# QuantumDice.net
KiCad netlist of a schematic drawn in EAGLE
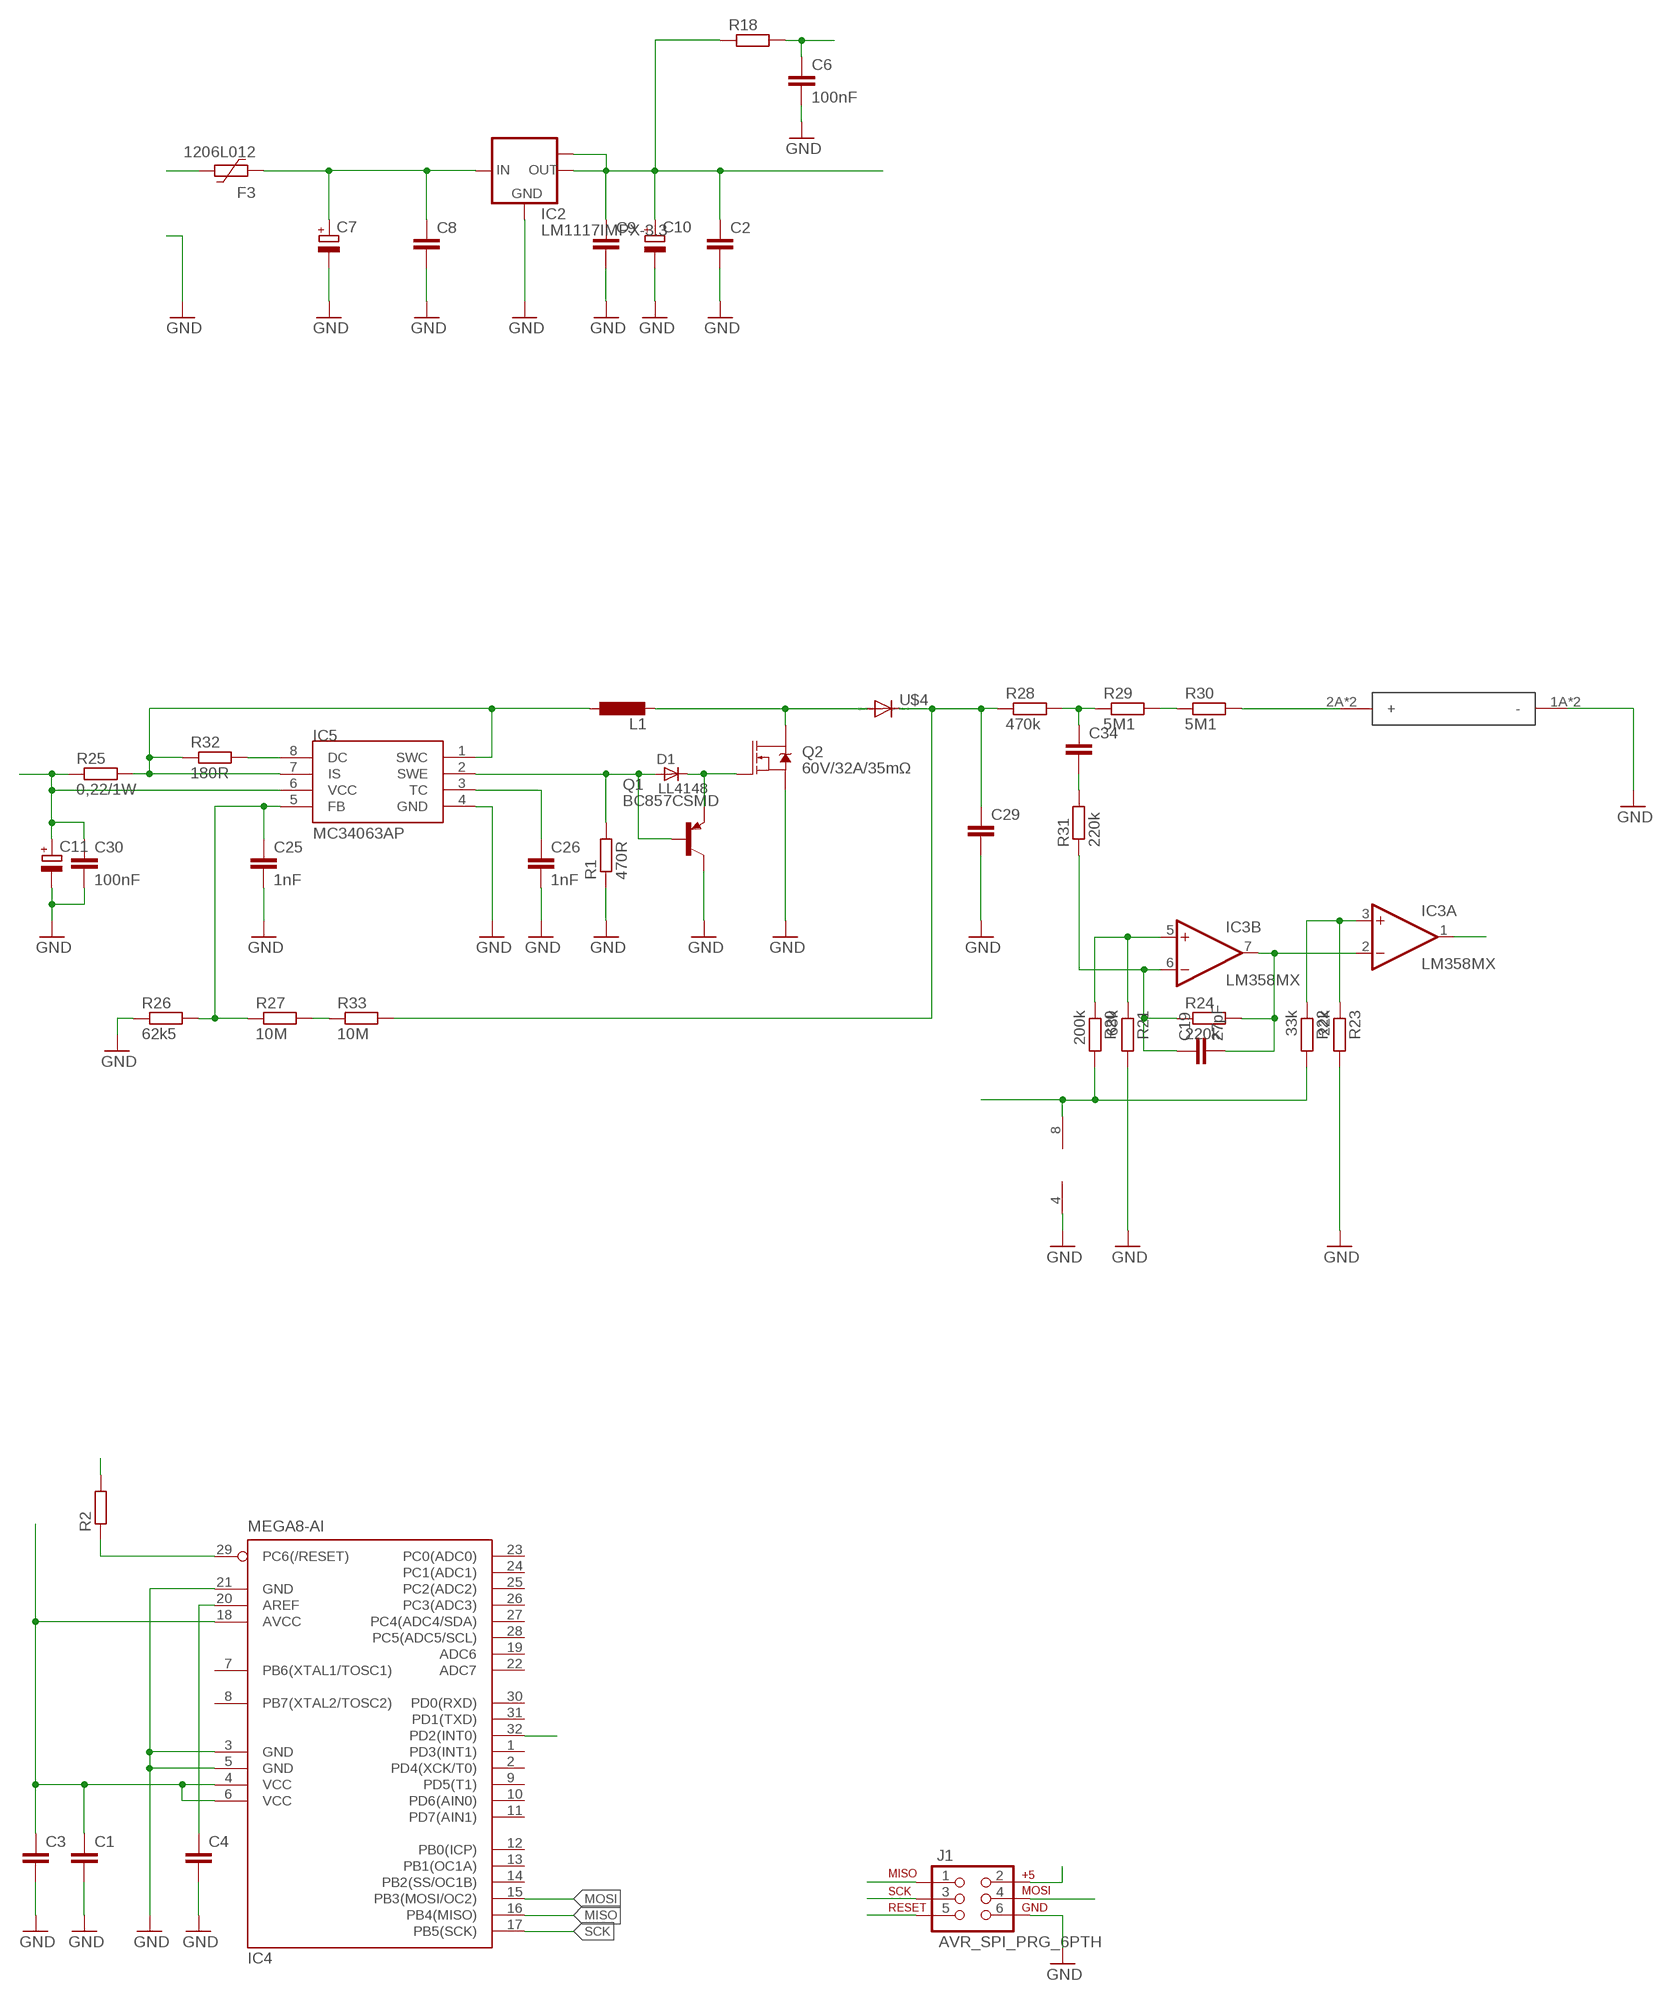
[diagram p0: schematic, sheet 1]

(export (version "E")
  (design (tool "Eeschema 10.0.6"))
  (components
    (comp (ref "C1")
      (value "C-EUC0603")
      (footprint "eagle-import:C0603")
      (libsource (lib "eagle-import") (part "C-EUC0603"))
    )
    (comp (ref "C2")
      (value "C-EUC0603")
      (footprint "eagle-import:C0603")
      (libsource (lib "eagle-import") (part "C-EUC0603"))
    )
    (comp (ref "C3")
      (value "C-EUC0603")
      (footprint "eagle-import:C0603")
      (libsource (lib "eagle-import") (part "C-EUC0603"))
    )
    (comp (ref "C4")
      (value "C-EUC0603")
      (footprint "eagle-import:C0603")
      (libsource (lib "eagle-import") (part "C-EUC0603"))
    )
    (comp (ref "C6")
      (value "100nF")
      (footprint "eagle-import:C0603")
      (libsource (lib "eagle-import") (part "C-EUC0603"))
    )
    (comp (ref "C7")
      (value "CPOL-EUSMCC")
      (footprint "eagle-import:SMC_C")
      (libsource (lib "eagle-import") (part "CPOL-EUSMCC"))
    )
    (comp (ref "C8")
      (value "C-EUC1206")
      (footprint "eagle-import:C1206")
      (libsource (lib "eagle-import") (part "C-EUC1206"))
    )
    (comp (ref "C9")
      (value "C-EUC1206")
      (footprint "eagle-import:C1206")
      (libsource (lib "eagle-import") (part "C-EUC1206"))
    )
    (comp (ref "C10")
      (value "CPOL-EUSMCC")
      (footprint "eagle-import:SMC_C")
      (libsource (lib "eagle-import") (part "CPOL-EUSMCC"))
    )
    (comp (ref "C11")
      (value "CPOL-EUSMCE")
      (footprint "eagle-import:SMC_E")
      (libsource (lib "eagle-import") (part "CPOL-EUSMCE"))
    )
    (comp (ref "C19")
      (value "27pF")
      (footprint "eagle-import:C0603")
      (libsource (lib "eagle-import") (part "C-EUC0603"))
    )
    (comp (ref "C25")
      (value "1nF")
      (footprint "eagle-import:C0603")
      (libsource (lib "eagle-import") (part "C-EUC0603"))
    )
    (comp (ref "C26")
      (value "1nF")
      (footprint "eagle-import:C0603")
      (libsource (lib "eagle-import") (part "C-EUC0603"))
    )
    (comp (ref "C29")
      (value "C-EU225-113X268")
      (footprint "eagle-import:C225-113X268")
      (libsource (lib "eagle-import") (part "C-EU225-113X268"))
    )
    (comp (ref "C30")
      (value "100nF")
      (footprint "eagle-import:C0603")
      (libsource (lib "eagle-import") (part "C-EUC0603"))
    )
    (comp (ref "C34")
      (value "C-EU050-024X044")
      (footprint "eagle-import:C050-024X044")
      (libsource (lib "eagle-import") (part "C-EU050-024X044"))
    )
    (comp (ref "D1")
      (value "LL4148")
      (footprint "eagle-import:SOD80_DO213AA_MINIMELF")
      (libsource (lib "eagle-import") (part "LL4148"))
    )
    (comp (ref "F3")
      (value "1206L012")
      (footprint "eagle-import:1206L")
      (fields (field (name "MF") "Littelfuse"))
      (libsource (lib "eagle-import") (part "?1206L012"))
    )
    (comp (ref "IC2")
      (value "LM1117IMPX-3.3")
      (footprint "eagle-import:SOT223")
      (libsource (lib "eagle-import") (part "LM1117IMPX-3.3"))
    )
    (comp (ref "IC3")
      (value "LM358MX")
      (footprint "eagle-import:SO08")
      (libsource (lib "eagle-import") (part "LM358MX"))
    )
    (comp (ref "IC4")
      (value "MEGA8-AI")
      (footprint "eagle-import:TQFP32-08")
      (fields (field (name "MPN") "ATMEGA8-16AU"))
      (libsource (lib "eagle-import") (part "MEGA8-AI"))
    )
    (comp (ref "IC5")
      (value "MC34063AP")
      (footprint "eagle-import:DIL08")
      (libsource (lib "eagle-import") (part "MC34063AP"))
    )
    (comp (ref "J1")
      (value "AVR_SPI_PRG_6PTH")
      (footprint "eagle-import:2X3")
      (libsource (lib "eagle-import") (part "AVR_SPI_PRG_6PTH"))
    )
    (comp (ref "L1")
      (value "L-EU6000-XXX-RC")
      (footprint "eagle-import:6000-XXXX-RC")
      (libsource (lib "eagle-import") (part "L-EU6000-XXX-RC"))
    )
    (comp (ref "Q1")
      (value "BC857CSMD")
      (footprint "eagle-import:SOT23-BEC")
      (libsource (lib "eagle-import") (part "BC857SMDC"))
    )
    (comp (ref "Q2")
      (value "60V/32A/35mΩ")
      (footprint "eagle-import:TO220V")
      (libsource (lib "eagle-import") (part "MOSFET-NCH-FQP30N06L"))
    )
    (comp (ref "R1")
      (value "470R")
      (footprint "eagle-import:R1206")
      (libsource (lib "eagle-import") (part "R-EU_R1206"))
    )
    (comp (ref "R2")
      (value "R-EU_R0603")
      (footprint "eagle-import:R0603")
      (libsource (lib "eagle-import") (part "R-EU_R0603"))
    )
    (comp (ref "R18")
      (value "R-EU_R1206")
      (footprint "eagle-import:R1206")
      (libsource (lib "eagle-import") (part "R-EU_R1206"))
    )
    (comp (ref "R20")
      (value "200k")
      (footprint "eagle-import:R0603")
      (libsource (lib "eagle-import") (part "R-EU_R0603"))
    )
    (comp (ref "R21")
      (value "68k")
      (footprint "eagle-import:R0603")
      (libsource (lib "eagle-import") (part "R-EU_R0603"))
    )
    (comp (ref "R22")
      (value "33k")
      (footprint "eagle-import:R1206")
      (libsource (lib "eagle-import") (part "R-EU_R1206"))
    )
    (comp (ref "R23")
      (value "22k")
      (footprint "eagle-import:R0603")
      (libsource (lib "eagle-import") (part "R-EU_R0603"))
    )
    (comp (ref "R24")
      (value "220k")
      (footprint "eagle-import:R0603")
      (libsource (lib "eagle-import") (part "R-EU_R0603"))
    )
    (comp (ref "R25")
      (value "0,22/1W")
      (footprint "eagle-import:R2010")
      (libsource (lib "eagle-import") (part "R-EU_R2010"))
    )
    (comp (ref "R26")
      (value "62k5")
      (footprint "eagle-import:R1206")
      (libsource (lib "eagle-import") (part "R-EU_R1206"))
    )
    (comp (ref "R27")
      (value "10M")
      (footprint "eagle-import:R2512")
      (libsource (lib "eagle-import") (part "R-EU_R2512"))
    )
    (comp (ref "R28")
      (value "470k")
      (footprint "eagle-import:R2512")
      (libsource (lib "eagle-import") (part "R-EU_R2512"))
    )
    (comp (ref "R29")
      (value "5M1")
      (footprint "eagle-import:R2512")
      (libsource (lib "eagle-import") (part "R-EU_R2512"))
    )
    (comp (ref "R30")
      (value "5M1")
      (footprint "eagle-import:R2512")
      (libsource (lib "eagle-import") (part "R-EU_R2512"))
    )
    (comp (ref "R31")
      (value "220k")
      (footprint "eagle-import:R0805")
      (libsource (lib "eagle-import") (part "R-EU_R0805"))
    )
    (comp (ref "R32")
      (value "180R")
      (footprint "eagle-import:R0805")
      (libsource (lib "eagle-import") (part "R-EU_R0805"))
    )
    (comp (ref "R33")
      (value "10M")
      (footprint "eagle-import:R2512")
      (libsource (lib "eagle-import") (part "R-EU_R2512"))
    )
    (comp (ref "U$4")
      (value "DIODE-MELF-MLL41")
      (footprint "eagle-import:MELF-MLL41")
      (libsource (lib "eagle-import") (part "DIODE-MELF-MLL41"))
    )
    (comp (ref "U$5")
      (value "STS5")
      (footprint "eagle-import:GEIGERTUBE")
      (libsource (lib "eagle-import") (part "STS5"))
    )
  )
  (nets
    (net (code "1") (name "/9V") (class "Default")
      (node (ref "C11") (pin "+") (pinfunction "+_+") (pintype "passive"))
      (node (ref "C30") (pin "1") (pinfunction "1_1") (pintype "passive"))
      (node (ref "C7") (pin "+") (pinfunction "+_+") (pintype "passive"))
      (node (ref "C8") (pin "1") (pinfunction "1_1") (pintype "passive"))
      (node (ref "F3") (pin "2") (pinfunction "2_2") (pintype "passive"))
      (node (ref "IC2") (pin "3") (pinfunction "IN_3") (pintype "input"))
      (node (ref "IC5") (pin "6") (pinfunction "VCC_6") (pintype "passive"))
      (node (ref "R25") (pin "1") (pinfunction "1_1") (pintype "passive"))
    )
    (net (code "2") (name "/A_5V") (class "Default")
      (node (ref "C6") (pin "1") (pinfunction "1_1") (pintype "passive"))
      (node (ref "IC3") (pin "8") (pinfunction "V+_8") (pintype "power_in"))
      (node (ref "R18") (pin "2") (pinfunction "2_2") (pintype "passive"))
      (node (ref "R20") (pin "2") (pinfunction "2_2") (pintype "passive"))
      (node (ref "R22") (pin "2") (pinfunction "2_2") (pintype "passive"))
    )
    (net (code "3") (name "/CPM") (class "Default")
      (node (ref "IC3") (pin "1") (pinfunction "OUT_1") (pintype "output"))
      (node (ref "IC4") (pin "32") (pinfunction "PD2(INT0)_32") (pintype "bidirectional"))
    )
    (net (code "4") (name "/RESET") (class "Default")
      (node (ref "IC4") (pin "29") (pinfunction "PC6(/RESET)_29") (pintype "bidirectional"))
      (node (ref "J1") (pin "5") (pinfunction "5_5") (pintype "passive"))
      (node (ref "R2") (pin "1") (pinfunction "1_1") (pintype "passive"))
    )
    (net (code "5") (name "/_5V") (class "Default")
      (node (ref "C1") (pin "1") (pinfunction "1_1") (pintype "passive"))
      (node (ref "C10") (pin "+") (pinfunction "+_+") (pintype "passive"))
      (node (ref "C2") (pin "1") (pinfunction "1_1") (pintype "passive"))
      (node (ref "C3") (pin "1") (pinfunction "1_1") (pintype "passive"))
      (node (ref "C9") (pin "1") (pinfunction "1_1") (pintype "passive"))
      (node (ref "IC2") (pin "2") (pinfunction "OUT_2") (pintype "passive"))
      (node (ref "IC2") (pin "TAB") (pinfunction "OUT1_TAB") (pintype "passive"))
      (node (ref "IC4") (pin "18") (pinfunction "AVCC_18") (pintype "power_in"))
      (node (ref "IC4") (pin "4") (pinfunction "VCC_4") (pintype "power_in"))
      (node (ref "IC4") (pin "6") (pinfunction "VCC_6") (pintype "power_in"))
      (node (ref "J1") (pin "2") (pinfunction "2_2") (pintype "passive"))
      (node (ref "R18") (pin "1") (pinfunction "1_1") (pintype "passive"))
      (node (ref "R2") (pin "2") (pinfunction "2_2") (pintype "passive"))
    )
    (net (code "6") (name "GND") (class "Default")
      (node (ref "C1") (pin "2") (pinfunction "2_2") (pintype "passive"))
      (node (ref "C10") (pin "-") (pinfunction "-_-") (pintype "passive"))
      (node (ref "C11") (pin "-") (pinfunction "-_-") (pintype "passive"))
      (node (ref "C2") (pin "2") (pinfunction "2_2") (pintype "passive"))
      (node (ref "C25") (pin "2") (pinfunction "2_2") (pintype "passive"))
      (node (ref "C26") (pin "2") (pinfunction "2_2") (pintype "passive"))
      (node (ref "C29") (pin "2") (pinfunction "2_2") (pintype "passive"))
      (node (ref "C3") (pin "2") (pinfunction "2_2") (pintype "passive"))
      (node (ref "C30") (pin "2") (pinfunction "2_2") (pintype "passive"))
      (node (ref "C4") (pin "2") (pinfunction "2_2") (pintype "passive"))
      (node (ref "C6") (pin "2") (pinfunction "2_2") (pintype "passive"))
      (node (ref "C7") (pin "-") (pinfunction "-_-") (pintype "passive"))
      (node (ref "C8") (pin "2") (pinfunction "2_2") (pintype "passive"))
      (node (ref "C9") (pin "2") (pinfunction "2_2") (pintype "passive"))
      (node (ref "IC2") (pin "1") (pinfunction "GND_1") (pintype "input"))
      (node (ref "IC3") (pin "4") (pinfunction "V-_4") (pintype "power_in"))
      (node (ref "IC4") (pin "21") (pinfunction "GND_21") (pintype "power_in"))
      (node (ref "IC4") (pin "3") (pinfunction "GND_3") (pintype "power_in"))
      (node (ref "IC4") (pin "5") (pinfunction "GND_5") (pintype "power_in"))
      (node (ref "IC5") (pin "4") (pinfunction "GND_4") (pintype "passive"))
      (node (ref "J1") (pin "6") (pinfunction "6_6") (pintype "passive"))
      (node (ref "Q1") (pin "C") (pinfunction "C_C") (pintype "passive"))
      (node (ref "Q2") (pin "3") (pinfunction "S_3") (pintype "bidirectional"))
      (node (ref "R1") (pin "1") (pinfunction "1_1") (pintype "passive"))
      (node (ref "R21") (pin "2") (pinfunction "2_2") (pintype "passive"))
      (node (ref "R23") (pin "2") (pinfunction "2_2") (pintype "passive"))
      (node (ref "R26") (pin "1") (pinfunction "1_1") (pintype "passive"))
      (node (ref "U$5") (pin "1A") (pinfunction "-_1A") (pintype "bidirectional"))
      (node (ref "U$5") (pin "1B") (pinfunction "-_1B") (pintype "bidirectional"))
    )
    (net (code "7") (name "MISO") (class "Default")
      (node (ref "IC4") (pin "16") (pinfunction "PB4(MISO)_16") (pintype "bidirectional"))
      (node (ref "J1") (pin "1") (pinfunction "1_1") (pintype "passive"))
    )
    (net (code "8") (name "MOSI") (class "Default")
      (node (ref "IC4") (pin "15") (pinfunction "PB3(MOSI/OC2)_15") (pintype "bidirectional"))
      (node (ref "J1") (pin "4") (pinfunction "4_4") (pintype "passive"))
    )
    (net (code "9") (name "Net-(C29-Pad1)") (class "Default")
      (node (ref "C29") (pin "1") (pinfunction "1_1") (pintype "passive"))
      (node (ref "R28") (pin "1") (pinfunction "1_1") (pintype "passive"))
      (node (ref "R33") (pin "2") (pinfunction "2_2") (pintype "passive"))
      (node (ref "U$4") (pin "C") (pinfunction "C_C") (pintype "passive"))
    )
    (net (code "10") (name "Net-(C34-Pad1)") (class "Default")
      (node (ref "C34") (pin "1") (pinfunction "1_1") (pintype "passive"))
      (node (ref "R28") (pin "2") (pinfunction "2_2") (pintype "passive"))
      (node (ref "R29") (pin "1") (pinfunction "1_1") (pintype "passive"))
    )
    (net (code "11") (name "Net-(C34-Pad2)") (class "Default")
      (node (ref "C34") (pin "2") (pinfunction "2_2") (pintype "passive"))
      (node (ref "R31") (pin "2") (pinfunction "2_2") (pintype "passive"))
    )
    (net (code "12") (name "Net-(IC3A-+IN)") (class "Default")
      (node (ref "IC3") (pin "3") (pinfunction "+IN_3") (pintype "input"))
      (node (ref "R22") (pin "1") (pinfunction "1_1") (pintype "passive"))
      (node (ref "R23") (pin "1") (pinfunction "1_1") (pintype "passive"))
    )
    (net (code "13") (name "Net-(IC3A--IN)") (class "Default")
      (node (ref "C19") (pin "2") (pinfunction "2_2") (pintype "passive"))
      (node (ref "IC3") (pin "2") (pinfunction "-IN_2") (pintype "input"))
      (node (ref "IC3") (pin "7") (pinfunction "OUT_7") (pintype "output"))
      (node (ref "R24") (pin "2") (pinfunction "2_2") (pintype "passive"))
    )
    (net (code "14") (name "Net-(IC3B-+IN)") (class "Default")
      (node (ref "IC3") (pin "5") (pinfunction "+IN_5") (pintype "input"))
      (node (ref "R20") (pin "1") (pinfunction "1_1") (pintype "passive"))
      (node (ref "R21") (pin "1") (pinfunction "1_1") (pintype "passive"))
    )
    (net (code "15") (name "Net-(IC3B--IN)") (class "Default")
      (node (ref "C19") (pin "1") (pinfunction "1_1") (pintype "passive"))
      (node (ref "IC3") (pin "6") (pinfunction "-IN_6") (pintype "input"))
      (node (ref "R24") (pin "1") (pinfunction "1_1") (pintype "passive"))
      (node (ref "R31") (pin "1") (pinfunction "1_1") (pintype "passive"))
    )
    (net (code "16") (name "Net-(IC4-AREF)") (class "Default")
      (node (ref "C4") (pin "1") (pinfunction "1_1") (pintype "passive"))
      (node (ref "IC4") (pin "20") (pinfunction "AREF_20") (pintype "passive"))
    )
    (net (code "17") (name "Net-(IC5-DC)") (class "Default")
      (node (ref "IC5") (pin "8") (pinfunction "DC_8") (pintype "passive"))
      (node (ref "R32") (pin "2") (pinfunction "2_2") (pintype "passive"))
    )
    (net (code "18") (name "Net-(IC5-FB)") (class "Default")
      (node (ref "C25") (pin "1") (pinfunction "1_1") (pintype "passive"))
      (node (ref "IC5") (pin "5") (pinfunction "FB_5") (pintype "passive"))
      (node (ref "R26") (pin "2") (pinfunction "2_2") (pintype "passive"))
      (node (ref "R27") (pin "1") (pinfunction "1_1") (pintype "passive"))
    )
    (net (code "19") (name "Net-(IC5-IS)") (class "Default")
      (node (ref "IC5") (pin "1") (pinfunction "SWC_1") (pintype "passive"))
      (node (ref "IC5") (pin "7") (pinfunction "IS_7") (pintype "passive"))
      (node (ref "L1") (pin "1") (pinfunction "1_1") (pintype "passive"))
      (node (ref "R25") (pin "2") (pinfunction "2_2") (pintype "passive"))
      (node (ref "R32") (pin "1") (pinfunction "1_1") (pintype "passive"))
    )
    (net (code "20") (name "Net-(IC5-SWE)") (class "Default")
      (node (ref "D1") (pin "A") (pinfunction "A_A") (pintype "passive"))
      (node (ref "IC5") (pin "2") (pinfunction "SWE_2") (pintype "passive"))
      (node (ref "Q1") (pin "B") (pinfunction "B_B") (pintype "passive"))
      (node (ref "R1") (pin "2") (pinfunction "2_2") (pintype "passive"))
    )
    (net (code "21") (name "Net-(IC5-TC)") (class "Default")
      (node (ref "C26") (pin "1") (pinfunction "1_1") (pintype "passive"))
      (node (ref "IC5") (pin "3") (pinfunction "TC_3") (pintype "passive"))
    )
    (net (code "22") (name "Net-(Q2-D)") (class "Default")
      (node (ref "L1") (pin "2") (pinfunction "2_2") (pintype "passive"))
      (node (ref "Q2") (pin "2") (pinfunction "D_2") (pintype "bidirectional"))
      (node (ref "U$4") (pin "A") (pinfunction "A_A") (pintype "passive"))
    )
    (net (code "23") (name "Net-(Q2-G)") (class "Default")
      (node (ref "D1") (pin "C") (pinfunction "C_C") (pintype "passive"))
      (node (ref "Q1") (pin "E") (pinfunction "E_E") (pintype "passive"))
      (node (ref "Q2") (pin "1") (pinfunction "G_1") (pintype "bidirectional"))
    )
    (net (code "24") (name "Net-(R27-Pad2)") (class "Default")
      (node (ref "R27") (pin "2") (pinfunction "2_2") (pintype "passive"))
      (node (ref "R33") (pin "1") (pinfunction "1_1") (pintype "passive"))
    )
    (net (code "25") (name "Net-(R29-Pad2)") (class "Default")
      (node (ref "R29") (pin "2") (pinfunction "2_2") (pintype "passive"))
      (node (ref "R30") (pin "1") (pinfunction "1_1") (pintype "passive"))
    )
    (net (code "26") (name "Net-(R30-Pad2)") (class "Default")
      (node (ref "R30") (pin "2") (pinfunction "2_2") (pintype "passive"))
      (node (ref "U$5") (pin "2A") (pinfunction "+_2A") (pintype "bidirectional"))
      (node (ref "U$5") (pin "2B") (pinfunction "+_2B") (pintype "bidirectional"))
    )
    (net (code "27") (name "SCK") (class "Default")
      (node (ref "IC4") (pin "17") (pinfunction "PB5(SCK)_17") (pintype "bidirectional"))
      (node (ref "J1") (pin "3") (pinfunction "3_3") (pintype "passive"))
    )
    (net (code "28") (name "unconnected-(F3-Pad1)") (class "Default")
      (node (ref "F3") (pin "1") (pinfunction "1_1") (pintype "passive"))
    )
    (net (code "29") (name "unconnected-(IC4-ADC6-Pad19)") (class "Default")
      (node (ref "IC4") (pin "19") (pinfunction "ADC6_19") (pintype "bidirectional"))
    )
    (net (code "30") (name "unconnected-(IC4-ADC7-Pad22)") (class "Default")
      (node (ref "IC4") (pin "22") (pinfunction "ADC7_22") (pintype "bidirectional"))
    )
    (net (code "31") (name "unconnected-(IC4-PB0(ICP)-Pad12)") (class "Default")
      (node (ref "IC4") (pin "12") (pinfunction "PB0(ICP)_12") (pintype "bidirectional"))
    )
    (net (code "32") (name "unconnected-(IC4-PB1(OC1A)-Pad13)") (class "Default")
      (node (ref "IC4") (pin "13") (pinfunction "PB1(OC1A)_13") (pintype "bidirectional"))
    )
    (net (code "33") (name "unconnected-(IC4-PB2(SS{slash}OC1B)-Pad14)") (class "Default")
      (node (ref "IC4") (pin "14") (pinfunction "PB2(SS/OC1B)_14") (pintype "bidirectional"))
    )
    (net (code "34") (name "unconnected-(IC4-PB6(XTAL1{slash}TOSC1)-Pad7)") (class "Default")
      (node (ref "IC4") (pin "7") (pinfunction "PB6(XTAL1/TOSC1)_7") (pintype "bidirectional"))
    )
    (net (code "35") (name "unconnected-(IC4-PB7(XTAL2{slash}TOSC2)-Pad8)") (class "Default")
      (node (ref "IC4") (pin "8") (pinfunction "PB7(XTAL2/TOSC2)_8") (pintype "bidirectional"))
    )
    (net (code "36") (name "unconnected-(IC4-PC0(ADC0)-Pad23)") (class "Default")
      (node (ref "IC4") (pin "23") (pinfunction "PC0(ADC0)_23") (pintype "bidirectional"))
    )
    (net (code "37") (name "unconnected-(IC4-PC1(ADC1)-Pad24)") (class "Default")
      (node (ref "IC4") (pin "24") (pinfunction "PC1(ADC1)_24") (pintype "bidirectional"))
    )
    (net (code "38") (name "unconnected-(IC4-PC2(ADC2)-Pad25)") (class "Default")
      (node (ref "IC4") (pin "25") (pinfunction "PC2(ADC2)_25") (pintype "bidirectional"))
    )
    (net (code "39") (name "unconnected-(IC4-PC3(ADC3)-Pad26)") (class "Default")
      (node (ref "IC4") (pin "26") (pinfunction "PC3(ADC3)_26") (pintype "bidirectional"))
    )
    (net (code "40") (name "unconnected-(IC4-PC4(ADC4{slash}SDA)-Pad27)") (class "Default")
      (node (ref "IC4") (pin "27") (pinfunction "PC4(ADC4/SDA)_27") (pintype "bidirectional"))
    )
    (net (code "41") (name "unconnected-(IC4-PC5(ADC5{slash}SCL)-Pad28)") (class "Default")
      (node (ref "IC4") (pin "28") (pinfunction "PC5(ADC5/SCL)_28") (pintype "bidirectional"))
    )
    (net (code "42") (name "unconnected-(IC4-PD0(RXD)-Pad30)") (class "Default")
      (node (ref "IC4") (pin "30") (pinfunction "PD0(RXD)_30") (pintype "bidirectional"))
    )
    (net (code "43") (name "unconnected-(IC4-PD1(TXD)-Pad31)") (class "Default")
      (node (ref "IC4") (pin "31") (pinfunction "PD1(TXD)_31") (pintype "bidirectional"))
    )
    (net (code "44") (name "unconnected-(IC4-PD3(INT1)-Pad1)") (class "Default")
      (node (ref "IC4") (pin "1") (pinfunction "PD3(INT1)_1") (pintype "bidirectional"))
    )
    (net (code "45") (name "unconnected-(IC4-PD4(XCK{slash}T0)-Pad2)") (class "Default")
      (node (ref "IC4") (pin "2") (pinfunction "PD4(XCK/T0)_2") (pintype "bidirectional"))
    )
    (net (code "46") (name "unconnected-(IC4-PD5(T1)-Pad9)") (class "Default")
      (node (ref "IC4") (pin "9") (pinfunction "PD5(T1)_9") (pintype "bidirectional"))
    )
    (net (code "47") (name "unconnected-(IC4-PD6(AIN0)-Pad10)") (class "Default")
      (node (ref "IC4") (pin "10") (pinfunction "PD6(AIN0)_10") (pintype "bidirectional"))
    )
    (net (code "48") (name "unconnected-(IC4-PD7(AIN1)-Pad11)") (class "Default")
      (node (ref "IC4") (pin "11") (pinfunction "PD7(AIN1)_11") (pintype "bidirectional"))
    )
  )
)
